# Slave_STM32F405RGT6.net
KiCad netlist of a schematic drawn in Altium Designer
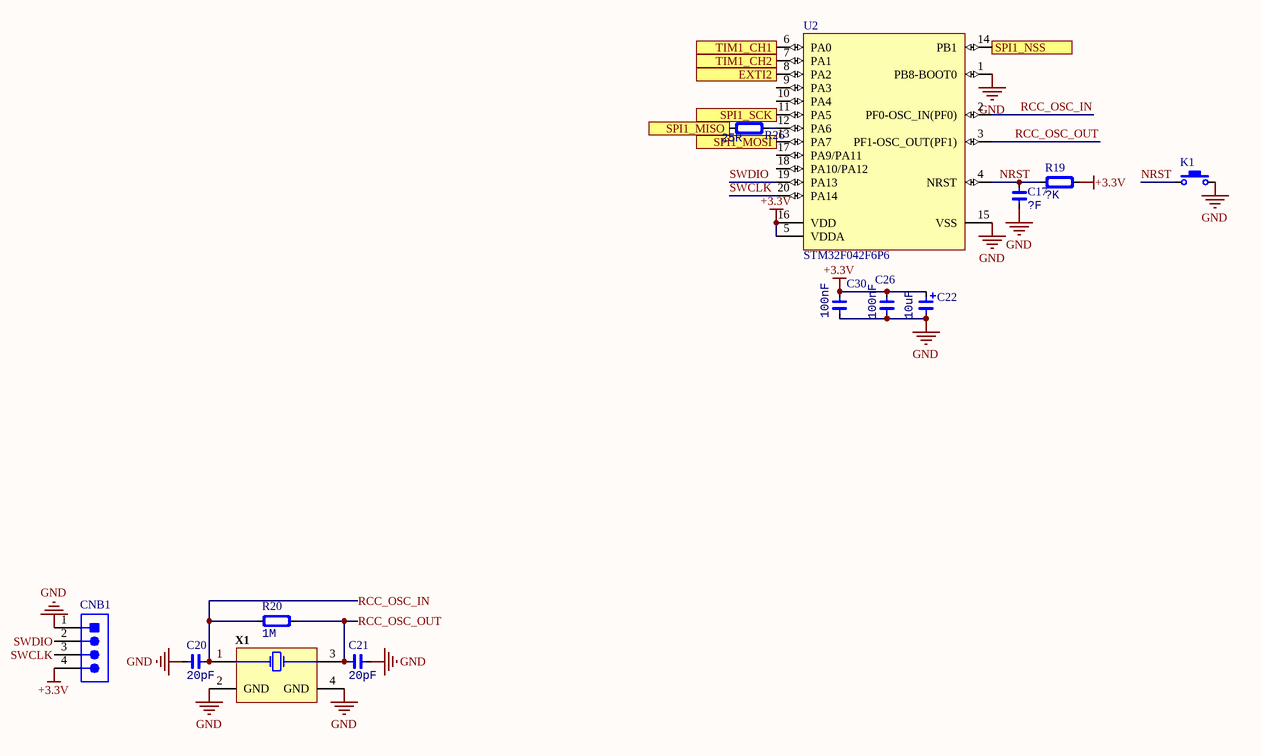
[diagram p0: [Slave]STM32F405RGT6.SchDoc]

(export (version "E")
  (design (tool "Eeschema 10.0.6"))
  (components
    (comp (ref "C17")
      (value "?F")
      (footprint "CAP-0603")
      (description "Capacitor")
      (fields (field (name "Comment") "Cap_0603"))
      (libsource (lib "") (part "Cap_0603_1"))
    )
    (comp (ref "C20")
      (value "20pF")
      (footprint "CAP-0603")
      (description "Capacitor")
      (fields (field (name "Comment") "Cap_0603"))
      (libsource (lib "Integrated_Library") (part "Cap_0603"))
    )
    (comp (ref "C21")
      (value "20pF")
      (footprint "CAP-0603")
      (description "Capacitor")
      (fields (field (name "Comment") "Cap_0603"))
      (libsource (lib "Integrated_Library") (part "Cap_0603"))
    )
    (comp (ref "C22")
      (value "10uF")
      (footprint "CAP_TAN_1206")
      (description "Capacitor Tantalum")
      (fields (field (name "Comment") "C1206"))
      (libsource (lib "Integrated_Library") (part "Cap_Tan_1206"))
    )
    (comp (ref "C26")
      (value "100nF")
      (footprint "CAP-0603")
      (description "Capacitor")
      (fields (field (name "Comment") "Cap_0603"))
      (libsource (lib "") (part "Cap_0603_1"))
    )
    (comp (ref "C30")
      (value "100nF")
      (footprint "CAP-0603")
      (description "Capacitor")
      (fields (field (name "Comment") "Cap_0603"))
      (libsource (lib "") (part "Cap_0603_1"))
    )
    (comp (ref "CNB1")
      (value "B4B-EH-A(LF)(SN)")
      (footprint "JST-B4B-EH-A_V")
      (fields (field (name "MANUFACTURER") "JST"))
      (libsource (lib "Altium Content Vault") (part "CN-1P-M-R4"))
    )
    (comp (ref "K1")
      (value "TACT")
      (footprint "ButtonTACT_3x4x2_180")
      (description "Button")
      (libsource (lib "Integrated_Library") (part "ButtonTACT_180_3x4x2"))
    )
    (comp (ref "R19")
      (value "?K")
      (footprint "RES-0603")
      (description "Resistor")
      (fields (field (name "Comment") "R0603"))
      (libsource (lib "Integrated_Library") (part "Res_0603"))
    )
    (comp (ref "R20")
      (value "1M")
      (footprint "RES-0603")
      (description "Resistor")
      (fields (field (name "Comment") "Res_0603"))
      (libsource (lib "Integrated_Library") (part "Res_0603"))
    )
    (comp (ref "R26")
      (value "25R")
      (footprint "RES-0805")
      (description "Resistor")
      (fields (field (name "Comment") "Res_0805"))
      (libsource (lib "Integrated_Library") (part "Res_0805"))
    )
    (comp (ref "U2")
      (value "STM32F042F6P6")
      (footprint "STM-TSSOP20_M")
      (fields (field (name "MANUFACTURER") "STMicroelectronics"))
      (libsource (lib "Altium Content Vault") (part "MC-ARM-STM32F042-TSSOP20"))
    )
    (comp (ref "X1")
      (value "7B-12.288MAAJ-T")
      (footprint "TXC-7B-4_V")
      (libsource (lib "Altium Content Vault") (part "XTAL-1-3-4"))
    )
  )
  (nets
    (net (code "1") (name "+3.3V") (class "Default")
      (node (ref "C22") (pin "1") (pinfunction "1_1") (pintype "passive"))
      (node (ref "C26") (pin "2") (pinfunction "2_2") (pintype "passive"))
      (node (ref "C30") (pin "2") (pinfunction "2_2") (pintype "passive"))
      (node (ref "CNB1") (pin "4") (pinfunction "4_4") (pintype "passive"))
      (node (ref "R19") (pin "2") (pinfunction "2_2") (pintype "passive"))
      (node (ref "U2") (pin "16") (pinfunction "VDD_16") (pintype "power_in"))
      (node (ref "U2") (pin "5") (pinfunction "VDDA_5") (pintype "power_in"))
    )
    (net (code "2") (name "/EXTI2") (class "Default")
      (node (ref "U2") (pin "8") (pinfunction "PA2_8") (pintype "bidirectional"))
    )
    (net (code "3") (name "/NRST") (class "Default")
      (node (ref "C17") (pin "2") (pinfunction "2_2") (pintype "passive"))
      (node (ref "K1") (pin "1") (pinfunction "1_1") (pintype "passive"))
      (node (ref "R19") (pin "1") (pinfunction "1_1") (pintype "passive"))
      (node (ref "U2") (pin "4") (pinfunction "NRST_4") (pintype "bidirectional"))
    )
    (net (code "4") (name "/RCC_OSC_IN") (class "Default")
      (node (ref "C20") (pin "1") (pinfunction "1_1") (pintype "passive"))
      (node (ref "R20") (pin "1") (pinfunction "1_1") (pintype "passive"))
      (node (ref "U2") (pin "2") (pinfunction "PF0-OSC_IN(PF0)_2") (pintype "bidirectional"))
      (node (ref "X1") (pin "1") (pinfunction "X1_1") (pintype "passive"))
    )
    (net (code "5") (name "/RCC_OSC_OUT") (class "Default")
      (node (ref "C21") (pin "2") (pinfunction "2_2") (pintype "passive"))
      (node (ref "R20") (pin "2") (pinfunction "2_2") (pintype "passive"))
      (node (ref "U2") (pin "3") (pinfunction "PF1-OSC_OUT(PF1)_3") (pintype "bidirectional"))
      (node (ref "X1") (pin "3") (pinfunction "X2_3") (pintype "passive"))
    )
    (net (code "6") (name "/SPI1_MISO") (class "Default")
      (node (ref "R26") (pin "1") (pinfunction "1_1") (pintype "passive"))
    )
    (net (code "7") (name "/SPI1_MOSI") (class "Default")
      (node (ref "U2") (pin "13") (pinfunction "PA7_13") (pintype "bidirectional"))
    )
    (net (code "8") (name "/SPI1_NSS") (class "Default")
      (node (ref "U2") (pin "14") (pinfunction "PB1_14") (pintype "bidirectional"))
    )
    (net (code "9") (name "/SPI1_SCK") (class "Default")
      (node (ref "U2") (pin "11") (pinfunction "PA5_11") (pintype "bidirectional"))
    )
    (net (code "10") (name "/SWCLK") (class "Default")
      (node (ref "CNB1") (pin "3") (pinfunction "3_3") (pintype "passive"))
      (node (ref "U2") (pin "20") (pinfunction "PA14_20") (pintype "bidirectional"))
    )
    (net (code "11") (name "/SWDIO") (class "Default")
      (node (ref "CNB1") (pin "2") (pinfunction "2_2") (pintype "passive"))
      (node (ref "U2") (pin "19") (pinfunction "PA13_19") (pintype "bidirectional"))
    )
    (net (code "12") (name "/TIM1_CH1") (class "Default")
      (node (ref "U2") (pin "6") (pinfunction "PA0_6") (pintype "bidirectional"))
    )
    (net (code "13") (name "/TIM1_CH2") (class "Default")
      (node (ref "U2") (pin "7") (pinfunction "PA1_7") (pintype "bidirectional"))
    )
    (net (code "14") (name "GND") (class "Default")
      (node (ref "C17") (pin "1") (pinfunction "1_1") (pintype "passive"))
      (node (ref "C20") (pin "2") (pinfunction "2_2") (pintype "passive"))
      (node (ref "C21") (pin "1") (pinfunction "1_1") (pintype "passive"))
      (node (ref "C22") (pin "2") (pinfunction "2_2") (pintype "passive"))
      (node (ref "C26") (pin "1") (pinfunction "1_1") (pintype "passive"))
      (node (ref "C30") (pin "1") (pinfunction "1_1") (pintype "passive"))
      (node (ref "CNB1") (pin "1") (pinfunction "1_1") (pintype "passive"))
      (node (ref "K1") (pin "2") (pinfunction "2_2") (pintype "passive"))
      (node (ref "U2") (pin "1") (pinfunction "PB8-BOOT0_1") (pintype "bidirectional"))
      (node (ref "U2") (pin "15") (pinfunction "VSS_15") (pintype "power_in"))
      (node (ref "X1") (pin "2") (pinfunction "GND_2") (pintype "power_in"))
      (node (ref "X1") (pin "4") (pinfunction "GND_4") (pintype "power_in"))
    )
    (net (code "15") (name "Net-(U2-PA6)") (class "Default")
      (node (ref "R26") (pin "2") (pinfunction "2_2") (pintype "passive"))
      (node (ref "U2") (pin "12") (pinfunction "PA6_12") (pintype "bidirectional"))
    )
    (net (code "16") (name "unconnected-(U2-PA3-Pad9)") (class "Default")
      (node (ref "U2") (pin "9") (pinfunction "PA3_9") (pintype "bidirectional"))
    )
    (net (code "17") (name "unconnected-(U2-PA4-Pad10)") (class "Default")
      (node (ref "U2") (pin "10") (pinfunction "PA4_10") (pintype "bidirectional"))
    )
    (net (code "18") (name "unconnected-(U2-PA9{slash}PA11-Pad17)") (class "Default")
      (node (ref "U2") (pin "17") (pinfunction "PA9/PA11_17") (pintype "bidirectional"))
    )
    (net (code "19") (name "unconnected-(U2-PA10{slash}PA12-Pad18)") (class "Default")
      (node (ref "U2") (pin "18") (pinfunction "PA10/PA12_18") (pintype "bidirectional"))
    )
  )
)
